# ver061_MCU.net
KiCad netlist of a schematic drawn in Altium Designer
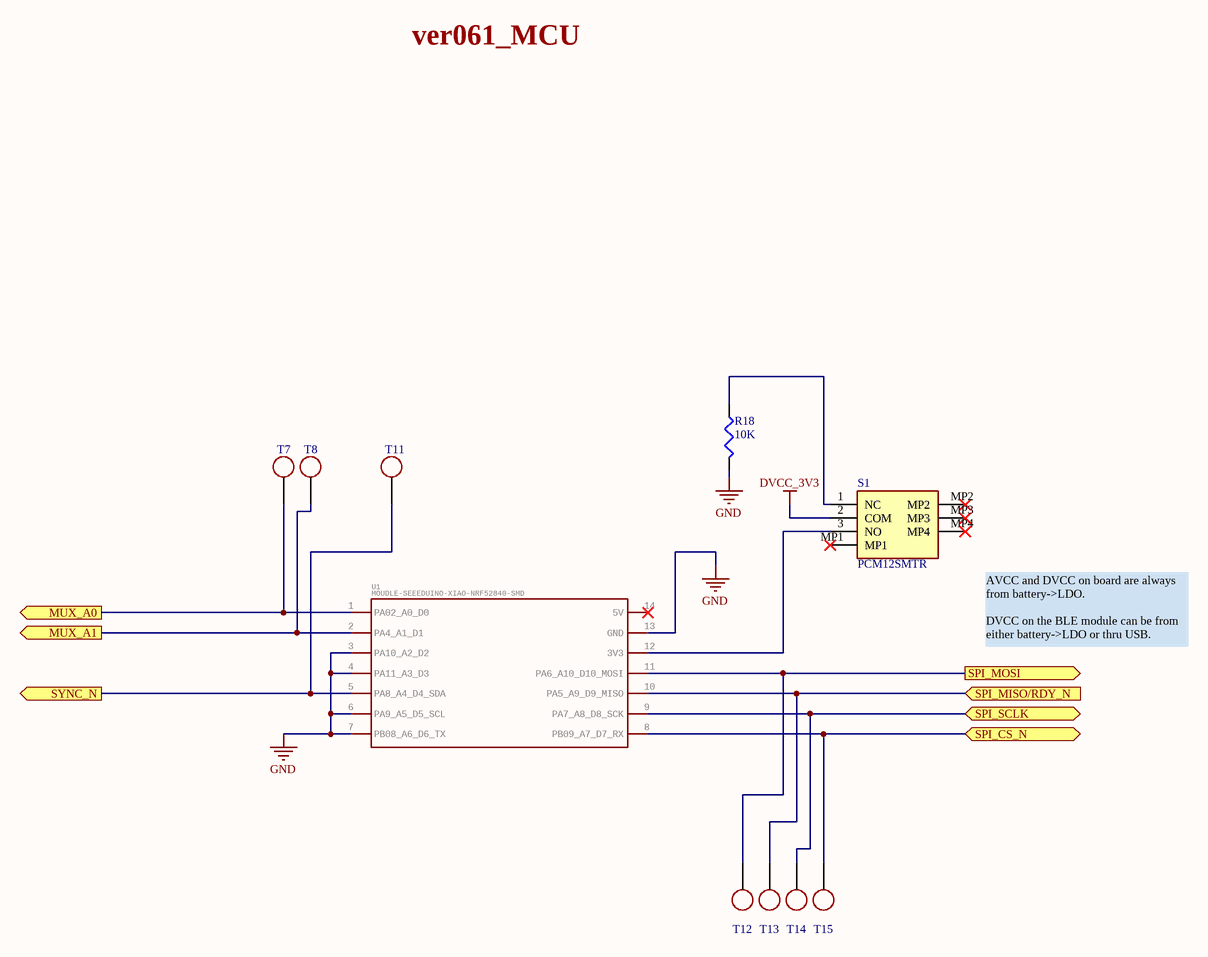
[diagram p0: ver061_MCU.SchDoc]

(export (version "E")
  (design (tool "Eeschema 10.0.6"))
  (components
    (comp (ref "R18")
      (value "10K")
      (footprint "RESC1005X35N")
      (description "Resistor")
      (fields (field (name "Comment") "Res3") (field (name "PUBLISHER") "Altium Limited"))
      (libsource (lib "Miscellaneous Devices") (part "Res3"))
    )
    (comp (ref "S1")
      (value "PCM12SMTR")
      (footprint "PCM12SMTR")
      (description "Switch")
      (fields (field (name "MOUSER PART NUMBER") "611-PCM12SMTR"))
      (libsource (lib "*") (part "PCM12SMTR"))
    )
    (comp (ref "T7")
      (value "TP_SMT")
      (footprint "TP_SMT_Round_0.6x0.6")
      (libsource (lib "nanowire") (part "TP_SMT"))
    )
    (comp (ref "T8")
      (value "TP_SMT")
      (footprint "TP_SMT_Round_0.6x0.6")
      (libsource (lib "nanowire") (part "TP_SMT"))
    )
    (comp (ref "T11")
      (value "TP_SMT")
      (footprint "TP_SMT_Round_0.6x0.6")
      (libsource (lib "nanowire") (part "TP_SMT"))
    )
    (comp (ref "T12")
      (value "TP_SMT")
      (footprint "TP_SMT_Round_0.6x0.6")
      (libsource (lib "nanowire") (part "TP_SMT"))
    )
    (comp (ref "T13")
      (value "TP_SMT")
      (footprint "TP_SMT_Round_0.6x0.6")
      (libsource (lib "nanowire") (part "TP_SMT"))
    )
    (comp (ref "T14")
      (value "TP_SMT")
      (footprint "TP_SMT_Round_0.6x0.6")
      (libsource (lib "nanowire") (part "TP_SMT"))
    )
    (comp (ref "T15")
      (value "TP_SMT")
      (footprint "TP_SMT_Round_0.6x0.6")
      (libsource (lib "nanowire") (part "TP_SMT"))
    )
    (comp (ref "U1")
      (value "MOUDLE-SEEEDUINO-XIAO-NRF52840-SMD")
      (footprint "MOUDLE16P-SMD-2-54-21X17-8MM")
      (fields (field (name "LIBRARYNAME") "Seeed-Studio-XIAO-nRF52840-footprint-eagle"))
      (libsource (lib "Seeed-Studio-XIAO-nRF52840-footprint-eagle") (part "MOUDLE-SEEEDUINO-XIAO-NRF52840-SMD"))
    )
  )
  (nets
    (net (code "1") (name "/MUX_A0") (class "Default")
      (node (ref "T7") (pin "1") (pinfunction "1_1") (pintype "passive"))
      (node (ref "U1") (pin "1") (pinfunction "PA02_A0_D0_1") (pintype "bidirectional"))
    )
    (net (code "2") (name "/MUX_A1") (class "Default")
      (node (ref "T8") (pin "1") (pinfunction "1_1") (pintype "passive"))
      (node (ref "U1") (pin "2") (pinfunction "PA4_A1_D1_2") (pintype "bidirectional"))
    )
    (net (code "3") (name "/SPI_CS_N") (class "Default")
      (node (ref "T15") (pin "1") (pinfunction "1_1") (pintype "passive"))
      (node (ref "U1") (pin "8") (pinfunction "PB09_A7_D7_RX_8") (pintype "bidirectional"))
    )
    (net (code "4") (name "/SPI_MISO{slash}RDY_N") (class "Default")
      (node (ref "T13") (pin "1") (pinfunction "1_1") (pintype "passive"))
      (node (ref "U1") (pin "10") (pinfunction "PA5_A9_D9_MISO_10") (pintype "bidirectional"))
    )
    (net (code "5") (name "/SPI_MOSI") (class "Default")
      (node (ref "T12") (pin "1") (pinfunction "1_1") (pintype "passive"))
      (node (ref "U1") (pin "11") (pinfunction "PA6_A10_D10_MOSI_11") (pintype "bidirectional"))
    )
    (net (code "6") (name "/SPI_SCLK") (class "Default")
      (node (ref "T14") (pin "1") (pinfunction "1_1") (pintype "passive"))
      (node (ref "U1") (pin "9") (pinfunction "PA7_A8_D8_SCK_9") (pintype "bidirectional"))
    )
    (net (code "7") (name "/SYNC_N") (class "Default")
      (node (ref "T11") (pin "1") (pinfunction "1_1") (pintype "passive"))
      (node (ref "U1") (pin "5") (pinfunction "PA8_A4_D4_SDA_5") (pintype "bidirectional"))
    )
    (net (code "8") (name "DVCC_3V3") (class "Default")
      (node (ref "S1") (pin "2") (pinfunction "COM_2") (pintype "passive"))
    )
    (net (code "9") (name "GND") (class "Default")
      (node (ref "R18") (pin "2") (pinfunction "2_2") (pintype "passive"))
      (node (ref "U1") (pin "13") (pinfunction "GND_13") (pintype "bidirectional"))
      (node (ref "U1") (pin "3") (pinfunction "PA10_A2_D2_3") (pintype "bidirectional"))
      (node (ref "U1") (pin "4") (pinfunction "PA11_A3_D3_4") (pintype "bidirectional"))
      (node (ref "U1") (pin "6") (pinfunction "PA9_A5_D5_SCL_6") (pintype "bidirectional"))
      (node (ref "U1") (pin "7") (pinfunction "PB08_A6_D6_TX_7") (pintype "bidirectional"))
    )
    (net (code "10") (name "Net-(S1-NC)") (class "Default")
      (node (ref "R18") (pin "1") (pinfunction "1_1") (pintype "passive"))
      (node (ref "S1") (pin "1") (pinfunction "NC_1") (pintype "passive"))
    )
    (net (code "11") (name "Net-(S1-NO)") (class "Default")
      (node (ref "S1") (pin "3") (pinfunction "NO_3") (pintype "passive"))
      (node (ref "U1") (pin "12") (pinfunction "3V3_12") (pintype "bidirectional"))
    )
    (net (code "12") (name "unconnected-(S1-PadMP1)") (class "Default")
      (node (ref "S1") (pin "MP1") (pinfunction "MP1_MP1") (pintype "passive+no_connect"))
    )
    (net (code "13") (name "unconnected-(S1-PadMP2)") (class "Default")
      (node (ref "S1") (pin "MP2") (pinfunction "MP2_MP2") (pintype "passive+no_connect"))
    )
    (net (code "14") (name "unconnected-(S1-PadMP3)") (class "Default")
      (node (ref "S1") (pin "MP3") (pinfunction "MP3_MP3") (pintype "passive+no_connect"))
    )
    (net (code "15") (name "unconnected-(S1-PadMP4)") (class "Default")
      (node (ref "S1") (pin "MP4") (pinfunction "MP4_MP4") (pintype "passive+no_connect"))
    )
    (net (code "16") (name "unconnected-(U1-5V-Pad14)") (class "Default")
      (node (ref "U1") (pin "14") (pinfunction "5V_14") (pintype "bidirectional+no_connect"))
    )
  )
)
